# FPGA_POWER.net
KiCad netlist of a schematic drawn in Altium Designer
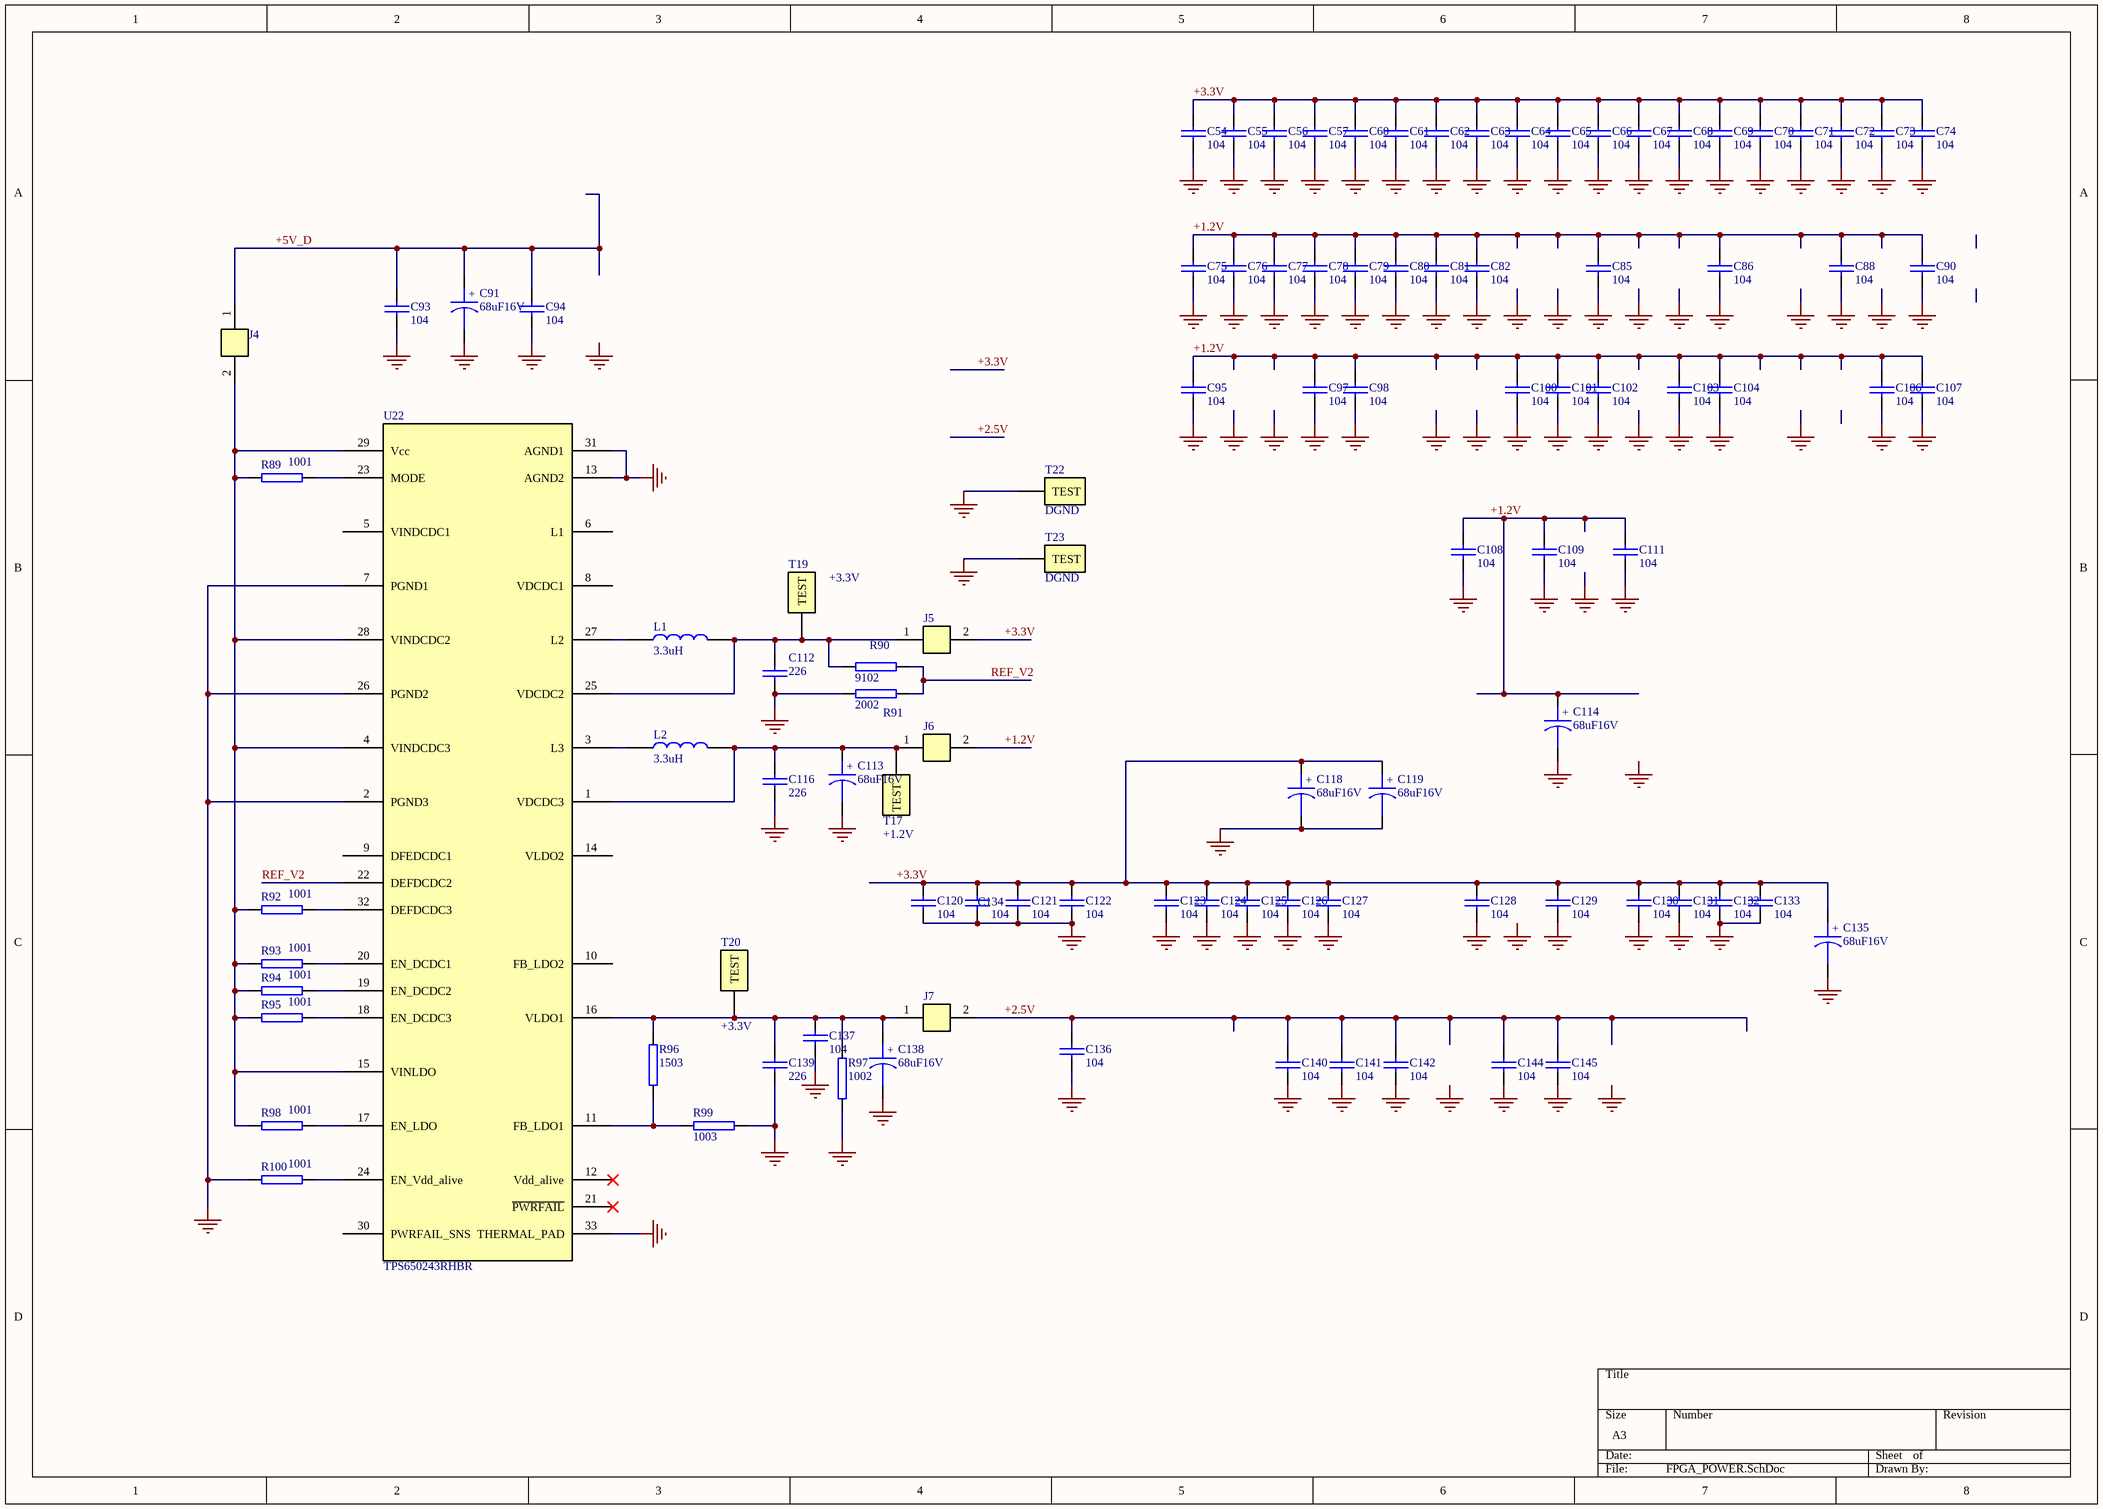
[diagram p0: FPGA_POWER.SchDoc]

(export (version "E")
  (design (tool "Eeschema 10.0.6"))
  (components
    (comp (ref "C54")
      (value "104")
      (footprint "0805C")
      (description "Capacitor")
      (libsource (lib "*") (part "CAP"))
    )
    (comp (ref "C55")
      (value "104")
      (footprint "0402C")
      (description "Capacitor")
      (libsource (lib "*") (part "CAP"))
    )
    (comp (ref "C56")
      (value "104")
      (footprint "0402C")
      (description "Capacitor")
      (libsource (lib "*") (part "CAP"))
    )
    (comp (ref "C57")
      (value "104")
      (footprint "0402C")
      (description "Capacitor")
      (libsource (lib "*") (part "CAP"))
    )
    (comp (ref "C60")
      (value "104")
      (footprint "0402C")
      (description "Capacitor")
      (libsource (lib "*") (part "CAP"))
    )
    (comp (ref "C61")
      (value "104")
      (footprint "0402C")
      (description "Capacitor")
      (libsource (lib "*") (part "CAP"))
    )
    (comp (ref "C62")
      (value "104")
      (footprint "0402C")
      (description "Capacitor")
      (libsource (lib "*") (part "CAP"))
    )
    (comp (ref "C63")
      (value "104")
      (footprint "0402C")
      (description "Capacitor")
      (libsource (lib "*") (part "CAP"))
    )
    (comp (ref "C64")
      (value "104")
      (footprint "0402C")
      (description "Capacitor")
      (libsource (lib "*") (part "CAP"))
    )
    (comp (ref "C65")
      (value "104")
      (footprint "0402C")
      (description "Capacitor")
      (libsource (lib "*") (part "CAP"))
    )
    (comp (ref "C66")
      (value "104")
      (footprint "0402C")
      (description "Capacitor")
      (libsource (lib "*") (part "CAP"))
    )
    (comp (ref "C67")
      (value "104")
      (footprint "0402C")
      (description "Capacitor")
      (libsource (lib "*") (part "CAP"))
    )
    (comp (ref "C68")
      (value "104")
      (footprint "0402C")
      (description "Capacitor")
      (libsource (lib "*") (part "CAP"))
    )
    (comp (ref "C69")
      (value "104")
      (footprint "0402C")
      (description "Capacitor")
      (libsource (lib "*") (part "CAP"))
    )
    (comp (ref "C70")
      (value "104")
      (footprint "0402C")
      (description "Capacitor")
      (libsource (lib "*") (part "CAP"))
    )
    (comp (ref "C71")
      (value "104")
      (footprint "0402C")
      (description "Capacitor")
      (libsource (lib "*") (part "CAP"))
    )
    (comp (ref "C72")
      (value "104")
      (footprint "0402C")
      (description "Capacitor")
      (libsource (lib "*") (part "CAP"))
    )
    (comp (ref "C73")
      (value "104")
      (footprint "0402C")
      (description "Capacitor")
      (libsource (lib "*") (part "CAP"))
    )
    (comp (ref "C74")
      (value "104")
      (footprint "0402C")
      (description "Capacitor")
      (libsource (lib "*") (part "CAP"))
    )
    (comp (ref "C75")
      (value "104")
      (footprint "0805C")
      (description "Capacitor")
      (libsource (lib "*") (part "CAP"))
    )
    (comp (ref "C76")
      (value "104")
      (footprint "0402C")
      (description "Capacitor")
      (libsource (lib "*") (part "CAP"))
    )
    (comp (ref "C77")
      (value "104")
      (footprint "0402C")
      (description "Capacitor")
      (libsource (lib "*") (part "CAP"))
    )
    (comp (ref "C78")
      (value "104")
      (footprint "0805C")
      (description "Capacitor")
      (libsource (lib "*") (part "CAP"))
    )
    (comp (ref "C79")
      (value "104")
      (footprint "0402C")
      (description "Capacitor")
      (libsource (lib "*") (part "CAP"))
    )
    (comp (ref "C80")
      (value "104")
      (footprint "0402C")
      (description "Capacitor")
      (libsource (lib "*") (part "CAP"))
    )
    (comp (ref "C81")
      (value "104")
      (footprint "0402C")
      (description "Capacitor")
      (libsource (lib "*") (part "CAP"))
    )
    (comp (ref "C82")
      (value "104")
      (footprint "0402C")
      (description "Capacitor")
      (libsource (lib "*") (part "CAP"))
    )
    (comp (ref "C85")
      (value "104")
      (footprint "0402C")
      (description "Capacitor")
      (libsource (lib "*") (part "CAP"))
    )
    (comp (ref "C86")
      (value "104")
      (footprint "0402C")
      (description "Capacitor")
      (libsource (lib "*") (part "CAP"))
    )
    (comp (ref "C88")
      (value "104")
      (footprint "0402C")
      (description "Capacitor")
      (libsource (lib "*") (part "CAP"))
    )
    (comp (ref "C90")
      (value "104")
      (footprint "0402C")
      (description "Capacitor")
      (libsource (lib "*") (part "CAP"))
    )
    (comp (ref "C91")
      (value "68uF16V")
      (footprint "6032")
      (description "Capacitor")
      (libsource (lib "*") (part "CAPACITOR POL"))
    )
    (comp (ref "C93")
      (value "104")
      (footprint "0805C")
      (description "Capacitor")
      (libsource (lib "*") (part "CAP"))
    )
    (comp (ref "C94")
      (value "104")
      (footprint "0805C")
      (description "Capacitor")
      (libsource (lib "*") (part "CAP"))
    )
    (comp (ref "C95")
      (value "104")
      (footprint "0402C")
      (description "Capacitor")
      (libsource (lib "*") (part "CAP"))
    )
    (comp (ref "C97")
      (value "104")
      (footprint "0402C")
      (description "Capacitor")
      (libsource (lib "*") (part "CAP"))
    )
    (comp (ref "C98")
      (value "104")
      (footprint "0402C")
      (description "Capacitor")
      (libsource (lib "*") (part "CAP"))
    )
    (comp (ref "C100")
      (value "104")
      (footprint "0402C")
      (description "Capacitor")
      (libsource (lib "*") (part "CAP"))
    )
    (comp (ref "C101")
      (value "104")
      (footprint "0402C")
      (description "Capacitor")
      (libsource (lib "*") (part "CAP"))
    )
    (comp (ref "C102")
      (value "104")
      (footprint "0402C")
      (description "Capacitor")
      (libsource (lib "*") (part "CAP"))
    )
    (comp (ref "C103")
      (value "104")
      (footprint "0402C")
      (description "Capacitor")
      (libsource (lib "*") (part "CAP"))
    )
    (comp (ref "C104")
      (value "104")
      (footprint "0402C")
      (description "Capacitor")
      (libsource (lib "*") (part "CAP"))
    )
    (comp (ref "C106")
      (value "104")
      (footprint "0402C")
      (description "Capacitor")
      (libsource (lib "*") (part "CAP"))
    )
    (comp (ref "C107")
      (value "104")
      (footprint "0402C")
      (description "Capacitor")
      (libsource (lib "*") (part "CAP"))
    )
    (comp (ref "C108")
      (value "104")
      (footprint "0402C")
      (description "Capacitor")
      (libsource (lib "*") (part "CAP"))
    )
    (comp (ref "C109")
      (value "104")
      (footprint "0402C")
      (description "Capacitor")
      (libsource (lib "*") (part "CAP"))
    )
    (comp (ref "C111")
      (value "104")
      (footprint "0402C")
      (description "Capacitor")
      (libsource (lib "*") (part "CAP"))
    )
    (comp (ref "C112")
      (value "226")
      (footprint "C226")
      (description "Capacitor")
      (libsource (lib "*") (part "CAP"))
    )
    (comp (ref "C113")
      (value "68uF16V")
      (footprint "6032")
      (description "Capacitor")
      (libsource (lib "*") (part "CAPACITOR POL"))
    )
    (comp (ref "C114")
      (value "68uF16V")
      (footprint "6032")
      (description "Capacitor")
      (libsource (lib "*") (part "CAPACITOR POL"))
    )
    (comp (ref "C116")
      (value "226")
      (footprint "C226")
      (description "Capacitor")
      (libsource (lib "*") (part "CAP"))
    )
    (comp (ref "C118")
      (value "68uF16V")
      (footprint "6032")
      (description "Capacitor")
      (libsource (lib "*") (part "CAPACITOR POL"))
    )
    (comp (ref "C119")
      (value "68uF16V")
      (footprint "6032")
      (description "Capacitor")
      (libsource (lib "*") (part "CAPACITOR POL"))
    )
    (comp (ref "C120")
      (value "104")
      (footprint "0402C")
      (description "Capacitor")
      (libsource (lib "*") (part "CAP"))
    )
    (comp (ref "C121")
      (value "104")
      (footprint "0402C")
      (description "Capacitor")
      (libsource (lib "*") (part "CAP"))
    )
    (comp (ref "C122")
      (value "104")
      (footprint "0805C")
      (description "Capacitor")
      (libsource (lib "*") (part "CAP"))
    )
    (comp (ref "C123")
      (value "104")
      (footprint "0805C")
      (description "Capacitor")
      (libsource (lib "*") (part "CAP"))
    )
    (comp (ref "C124")
      (value "104")
      (footprint "0805C")
      (description "Capacitor")
      (libsource (lib "*") (part "CAP"))
    )
    (comp (ref "C125")
      (value "104")
      (footprint "0805C")
      (description "Capacitor")
      (libsource (lib "*") (part "CAP"))
    )
    (comp (ref "C126")
      (value "104")
      (footprint "0805C")
      (description "Capacitor")
      (libsource (lib "*") (part "CAP"))
    )
    (comp (ref "C127")
      (value "104")
      (footprint "0402C")
      (description "Capacitor")
      (libsource (lib "*") (part "CAP"))
    )
    (comp (ref "C128")
      (value "104")
      (footprint "0805C")
      (description "Capacitor")
      (libsource (lib "*") (part "CAP"))
    )
    (comp (ref "C129")
      (value "104")
      (footprint "0402C")
      (description "Capacitor")
      (libsource (lib "*") (part "CAP"))
    )
    (comp (ref "C130")
      (value "104")
      (footprint "0402C")
      (description "Capacitor")
      (libsource (lib "*") (part "CAP"))
    )
    (comp (ref "C131")
      (value "104")
      (footprint "0402C")
      (description "Capacitor")
      (libsource (lib "*") (part "CAP"))
    )
    (comp (ref "C132")
      (value "104")
      (footprint "0402C")
      (description "Capacitor")
      (libsource (lib "*") (part "CAP"))
    )
    (comp (ref "C133")
      (value "104")
      (footprint "0402C")
      (description "Capacitor")
      (libsource (lib "*") (part "CAP"))
    )
    (comp (ref "C134")
      (value "104")
      (footprint "0402C")
      (description "Capacitor")
      (libsource (lib "*") (part "CAP"))
    )
    (comp (ref "C135")
      (value "68uF16V")
      (footprint "6032")
      (description "Capacitor")
      (libsource (lib "*") (part "CAPACITOR POL"))
    )
    (comp (ref "C136")
      (value "104")
      (footprint "0805C")
      (description "Capacitor")
      (libsource (lib "*") (part "CAP"))
    )
    (comp (ref "C137")
      (value "104")
      (footprint "0805C")
      (description "Capacitor")
      (libsource (lib "*") (part "CAP"))
    )
    (comp (ref "C138")
      (value "68uF16V")
      (footprint "6032")
      (description "Capacitor")
      (libsource (lib "*") (part "CAPACITOR POL"))
    )
    (comp (ref "C139")
      (value "226")
      (footprint "C226")
      (description "Capacitor")
      (libsource (lib "*") (part "CAP"))
    )
    (comp (ref "C140")
      (value "104")
      (footprint "0402C")
      (description "Capacitor")
      (libsource (lib "*") (part "CAP"))
    )
    (comp (ref "C141")
      (value "104")
      (footprint "0402C")
      (description "Capacitor")
      (libsource (lib "*") (part "CAP"))
    )
    (comp (ref "C142")
      (value "104")
      (footprint "0402C")
      (description "Capacitor")
      (libsource (lib "*") (part "CAP"))
    )
    (comp (ref "C144")
      (value "104")
      (footprint "0805C")
      (description "Capacitor")
      (libsource (lib "*") (part "CAP"))
    )
    (comp (ref "C145")
      (value "104")
      (footprint "0402C")
      (description "Capacitor")
      (libsource (lib "*") (part "CAP"))
    )
    (comp (ref "J4") (value "~") (footprint "I_ON1") (libsource (lib "") (part "I_ON_1")))
    (comp (ref "J5") (value "~") (footprint "I_ON1") (libsource (lib "*") (part "I_ON")))
    (comp (ref "J6") (value "~") (footprint "I_ON1") (libsource (lib "*") (part "I_ON")))
    (comp (ref "J7") (value "~") (footprint "I_ON1") (libsource (lib "*") (part "I_ON")))
    (comp (ref "L1") (value "3.3uH") (footprint "L3R3") (libsource (lib "*") (part "L")))
    (comp (ref "L2") (value "3.3uH") (footprint "L3R3") (libsource (lib "*") (part "L")))
    (comp (ref "R89") (value "1001") (footprint "0603") (libsource (lib "*") (part "RES2")))
    (comp (ref "R90") (value "9102") (footprint "0603") (libsource (lib "*") (part "RES2")))
    (comp (ref "R91") (value "2002") (footprint "0603") (libsource (lib "*") (part "RES2")))
    (comp (ref "R92") (value "1001") (footprint "0603") (libsource (lib "*") (part "RES2")))
    (comp (ref "R93") (value "1001") (footprint "0603") (libsource (lib "*") (part "RES2")))
    (comp (ref "R94") (value "1001") (footprint "0603") (libsource (lib "*") (part "RES2")))
    (comp (ref "R95") (value "1001") (footprint "0603") (libsource (lib "*") (part "RES2")))
    (comp (ref "R96") (value "1503") (footprint "0603") (libsource (lib "*") (part "RES2")))
    (comp (ref "R97") (value "1002") (footprint "0603") (libsource (lib "") (part "RES2_1")))
    (comp (ref "R98") (value "1001") (footprint "0603") (libsource (lib "*") (part "RES2")))
    (comp (ref "R99") (value "1003") (footprint "0603") (libsource (lib "*") (part "RES2")))
    (comp (ref "R100") (value "1001") (footprint "0603") (libsource (lib "*") (part "RES2")))
    (comp (ref "T17") (value "+1.2V") (footprint "TEST") (libsource (lib "USB30_Project") (part "TEST")))
    (comp (ref "T19") (value "+3.3V") (footprint "TEST") (libsource (lib "") (part "TEST_1")))
    (comp (ref "T20") (value "+3.3V") (footprint "TEST") (libsource (lib "") (part "TEST_1")))
    (comp (ref "T22") (value "DGND") (footprint "TEST") (libsource (lib "") (part "TEST_2")))
    (comp (ref "T23") (value "DGND") (footprint "TEST") (libsource (lib "") (part "TEST_2")))
    (comp (ref "U22") (value "TPS650243RHBR") (footprint "VQFN32") (libsource (lib "*") (part "TPS650243")))
  )
  (nets
    (net (code "1") (name "/+1.2V") (class "Default")
      (node (ref "C100") (pin "2") (pinfunction "2_2") (pintype "passive"))
      (node (ref "C101") (pin "2") (pinfunction "2_2") (pintype "passive"))
      (node (ref "C102") (pin "2") (pinfunction "2_2") (pintype "passive"))
      (node (ref "C103") (pin "2") (pinfunction "2_2") (pintype "passive"))
      (node (ref "C104") (pin "2") (pinfunction "2_2") (pintype "passive"))
      (node (ref "C106") (pin "2") (pinfunction "2_2") (pintype "passive"))
      (node (ref "C107") (pin "2") (pinfunction "2_2") (pintype "passive"))
      (node (ref "C108") (pin "2") (pinfunction "2_2") (pintype "passive"))
      (node (ref "C109") (pin "2") (pinfunction "2_2") (pintype "passive"))
      (node (ref "C111") (pin "2") (pinfunction "2_2") (pintype "passive"))
      (node (ref "C114") (pin "1") (pinfunction "1_1") (pintype "passive"))
      (node (ref "C75") (pin "2") (pinfunction "2_2") (pintype "passive"))
      (node (ref "C76") (pin "2") (pinfunction "2_2") (pintype "passive"))
      (node (ref "C77") (pin "2") (pinfunction "2_2") (pintype "passive"))
      (node (ref "C78") (pin "2") (pinfunction "2_2") (pintype "passive"))
      (node (ref "C79") (pin "2") (pinfunction "2_2") (pintype "passive"))
      (node (ref "C80") (pin "2") (pinfunction "2_2") (pintype "passive"))
      (node (ref "C81") (pin "2") (pinfunction "2_2") (pintype "passive"))
      (node (ref "C82") (pin "2") (pinfunction "2_2") (pintype "passive"))
      (node (ref "C85") (pin "2") (pinfunction "2_2") (pintype "passive"))
      (node (ref "C86") (pin "2") (pinfunction "2_2") (pintype "passive"))
      (node (ref "C88") (pin "2") (pinfunction "2_2") (pintype "passive"))
      (node (ref "C90") (pin "2") (pinfunction "2_2") (pintype "passive"))
      (node (ref "C95") (pin "2") (pinfunction "2_2") (pintype "passive"))
      (node (ref "C97") (pin "2") (pinfunction "2_2") (pintype "passive"))
      (node (ref "C98") (pin "2") (pinfunction "2_2") (pintype "passive"))
      (node (ref "J6") (pin "2") (pintype "passive"))
    )
    (net (code "2") (name "/+2.5V") (class "Default")
      (node (ref "C136") (pin "2") (pinfunction "2_2") (pintype "passive"))
      (node (ref "C140") (pin "2") (pinfunction "2_2") (pintype "passive"))
      (node (ref "C141") (pin "2") (pinfunction "2_2") (pintype "passive"))
      (node (ref "C142") (pin "2") (pinfunction "2_2") (pintype "passive"))
      (node (ref "C144") (pin "2") (pinfunction "2_2") (pintype "passive"))
      (node (ref "C145") (pin "2") (pinfunction "2_2") (pintype "passive"))
      (node (ref "J7") (pin "2") (pintype "passive"))
    )
    (net (code "3") (name "/+3.3V") (class "Default")
      (node (ref "C118") (pin "1") (pinfunction "1_1") (pintype "passive"))
      (node (ref "C119") (pin "1") (pinfunction "1_1") (pintype "passive"))
      (node (ref "C120") (pin "2") (pinfunction "2_2") (pintype "passive"))
      (node (ref "C121") (pin "2") (pinfunction "2_2") (pintype "passive"))
      (node (ref "C122") (pin "2") (pinfunction "2_2") (pintype "passive"))
      (node (ref "C123") (pin "2") (pinfunction "2_2") (pintype "passive"))
      (node (ref "C124") (pin "2") (pinfunction "2_2") (pintype "passive"))
      (node (ref "C125") (pin "2") (pinfunction "2_2") (pintype "passive"))
      (node (ref "C126") (pin "2") (pinfunction "2_2") (pintype "passive"))
      (node (ref "C127") (pin "2") (pinfunction "2_2") (pintype "passive"))
      (node (ref "C128") (pin "2") (pinfunction "2_2") (pintype "passive"))
      (node (ref "C129") (pin "2") (pinfunction "2_2") (pintype "passive"))
      (node (ref "C130") (pin "2") (pinfunction "2_2") (pintype "passive"))
      (node (ref "C131") (pin "2") (pinfunction "2_2") (pintype "passive"))
      (node (ref "C132") (pin "2") (pinfunction "2_2") (pintype "passive"))
      (node (ref "C133") (pin "2") (pinfunction "2_2") (pintype "passive"))
      (node (ref "C134") (pin "2") (pinfunction "2_2") (pintype "passive"))
      (node (ref "C135") (pin "1") (pinfunction "1_1") (pintype "passive"))
      (node (ref "C54") (pin "2") (pinfunction "2_2") (pintype "passive"))
      (node (ref "C55") (pin "2") (pinfunction "2_2") (pintype "passive"))
      (node (ref "C56") (pin "2") (pinfunction "2_2") (pintype "passive"))
      (node (ref "C57") (pin "2") (pinfunction "2_2") (pintype "passive"))
      (node (ref "C60") (pin "2") (pinfunction "2_2") (pintype "passive"))
      (node (ref "C61") (pin "2") (pinfunction "2_2") (pintype "passive"))
      (node (ref "C62") (pin "2") (pinfunction "2_2") (pintype "passive"))
      (node (ref "C63") (pin "2") (pinfunction "2_2") (pintype "passive"))
      (node (ref "C64") (pin "2") (pinfunction "2_2") (pintype "passive"))
      (node (ref "C65") (pin "2") (pinfunction "2_2") (pintype "passive"))
      (node (ref "C66") (pin "2") (pinfunction "2_2") (pintype "passive"))
      (node (ref "C67") (pin "2") (pinfunction "2_2") (pintype "passive"))
      (node (ref "C68") (pin "2") (pinfunction "2_2") (pintype "passive"))
      (node (ref "C69") (pin "2") (pinfunction "2_2") (pintype "passive"))
      (node (ref "C70") (pin "2") (pinfunction "2_2") (pintype "passive"))
      (node (ref "C71") (pin "2") (pinfunction "2_2") (pintype "passive"))
      (node (ref "C72") (pin "2") (pinfunction "2_2") (pintype "passive"))
      (node (ref "C73") (pin "2") (pinfunction "2_2") (pintype "passive"))
      (node (ref "C74") (pin "2") (pinfunction "2_2") (pintype "passive"))
      (node (ref "J5") (pin "2") (pintype "passive"))
    )
    (net (code "4") (name "/+5V_D") (class "Default")
      (node (ref "C91") (pin "1") (pinfunction "1_1") (pintype "passive"))
      (node (ref "C93") (pin "2") (pinfunction "2_2") (pintype "passive"))
      (node (ref "C94") (pin "2") (pinfunction "2_2") (pintype "passive"))
      (node (ref "J4") (pin "1") (pintype "passive"))
    )
    (net (code "5") (name "/REF_V2") (class "Default")
      (node (ref "R90") (pin "2") (pinfunction "2_2") (pintype "passive"))
      (node (ref "R91") (pin "1") (pinfunction "1_1") (pintype "passive"))
      (node (ref "U22") (pin "22") (pinfunction "DEFDCDC2_22") (pintype "passive"))
    )
    (net (code "6") (name "DGND") (class "Default")
      (node (ref "C100") (pin "1") (pinfunction "1_1") (pintype "passive"))
      (node (ref "C101") (pin "1") (pinfunction "1_1") (pintype "passive"))
      (node (ref "C102") (pin "1") (pinfunction "1_1") (pintype "passive"))
      (node (ref "C103") (pin "1") (pinfunction "1_1") (pintype "passive"))
      (node (ref "C104") (pin "1") (pinfunction "1_1") (pintype "passive"))
      (node (ref "C106") (pin "1") (pinfunction "1_1") (pintype "passive"))
      (node (ref "C107") (pin "1") (pinfunction "1_1") (pintype "passive"))
      (node (ref "C108") (pin "1") (pinfunction "1_1") (pintype "passive"))
      (node (ref "C109") (pin "1") (pinfunction "1_1") (pintype "passive"))
      (node (ref "C111") (pin "1") (pinfunction "1_1") (pintype "passive"))
      (node (ref "C112") (pin "2") (pinfunction "2_2") (pintype "passive"))
      (node (ref "C113") (pin "2") (pinfunction "2_2") (pintype "passive"))
      (node (ref "C114") (pin "2") (pinfunction "2_2") (pintype "passive"))
      (node (ref "C116") (pin "2") (pinfunction "2_2") (pintype "passive"))
      (node (ref "C118") (pin "2") (pinfunction "2_2") (pintype "passive"))
      (node (ref "C119") (pin "2") (pinfunction "2_2") (pintype "passive"))
      (node (ref "C120") (pin "1") (pinfunction "1_1") (pintype "passive"))
      (node (ref "C121") (pin "1") (pinfunction "1_1") (pintype "passive"))
      (node (ref "C122") (pin "1") (pinfunction "1_1") (pintype "passive"))
      (node (ref "C123") (pin "1") (pinfunction "1_1") (pintype "passive"))
      (node (ref "C124") (pin "1") (pinfunction "1_1") (pintype "passive"))
      (node (ref "C125") (pin "1") (pinfunction "1_1") (pintype "passive"))
      (node (ref "C126") (pin "1") (pinfunction "1_1") (pintype "passive"))
      (node (ref "C127") (pin "1") (pinfunction "1_1") (pintype "passive"))
      (node (ref "C128") (pin "1") (pinfunction "1_1") (pintype "passive"))
      (node (ref "C129") (pin "1") (pinfunction "1_1") (pintype "passive"))
      (node (ref "C130") (pin "1") (pinfunction "1_1") (pintype "passive"))
      (node (ref "C131") (pin "1") (pinfunction "1_1") (pintype "passive"))
      (node (ref "C132") (pin "1") (pinfunction "1_1") (pintype "passive"))
      (node (ref "C133") (pin "1") (pinfunction "1_1") (pintype "passive"))
      (node (ref "C134") (pin "1") (pinfunction "1_1") (pintype "passive"))
      (node (ref "C135") (pin "2") (pinfunction "2_2") (pintype "passive"))
      (node (ref "C136") (pin "1") (pinfunction "1_1") (pintype "passive"))
      (node (ref "C137") (pin "1") (pinfunction "1_1") (pintype "passive"))
      (node (ref "C138") (pin "2") (pinfunction "2_2") (pintype "passive"))
      (node (ref "C139") (pin "2") (pinfunction "2_2") (pintype "passive"))
      (node (ref "C140") (pin "1") (pinfunction "1_1") (pintype "passive"))
      (node (ref "C141") (pin "1") (pinfunction "1_1") (pintype "passive"))
      (node (ref "C142") (pin "1") (pinfunction "1_1") (pintype "passive"))
      (node (ref "C144") (pin "1") (pinfunction "1_1") (pintype "passive"))
      (node (ref "C145") (pin "1") (pinfunction "1_1") (pintype "passive"))
      (node (ref "C54") (pin "1") (pinfunction "1_1") (pintype "passive"))
      (node (ref "C55") (pin "1") (pinfunction "1_1") (pintype "passive"))
      (node (ref "C56") (pin "1") (pinfunction "1_1") (pintype "passive"))
      (node (ref "C57") (pin "1") (pinfunction "1_1") (pintype "passive"))
      (node (ref "C60") (pin "1") (pinfunction "1_1") (pintype "passive"))
      (node (ref "C61") (pin "1") (pinfunction "1_1") (pintype "passive"))
      (node (ref "C62") (pin "1") (pinfunction "1_1") (pintype "passive"))
      (node (ref "C63") (pin "1") (pinfunction "1_1") (pintype "passive"))
      (node (ref "C64") (pin "1") (pinfunction "1_1") (pintype "passive"))
      (node (ref "C65") (pin "1") (pinfunction "1_1") (pintype "passive"))
      (node (ref "C66") (pin "1") (pinfunction "1_1") (pintype "passive"))
      (node (ref "C67") (pin "1") (pinfunction "1_1") (pintype "passive"))
      (node (ref "C68") (pin "1") (pinfunction "1_1") (pintype "passive"))
      (node (ref "C69") (pin "1") (pinfunction "1_1") (pintype "passive"))
      (node (ref "C70") (pin "1") (pinfunction "1_1") (pintype "passive"))
      (node (ref "C71") (pin "1") (pinfunction "1_1") (pintype "passive"))
      (node (ref "C72") (pin "1") (pinfunction "1_1") (pintype "passive"))
      (node (ref "C73") (pin "1") (pinfunction "1_1") (pintype "passive"))
      (node (ref "C74") (pin "1") (pinfunction "1_1") (pintype "passive"))
      (node (ref "C75") (pin "1") (pinfunction "1_1") (pintype "passive"))
      (node (ref "C76") (pin "1") (pinfunction "1_1") (pintype "passive"))
      (node (ref "C77") (pin "1") (pinfunction "1_1") (pintype "passive"))
      (node (ref "C78") (pin "1") (pinfunction "1_1") (pintype "passive"))
      (node (ref "C79") (pin "1") (pinfunction "1_1") (pintype "passive"))
      (node (ref "C80") (pin "1") (pinfunction "1_1") (pintype "passive"))
      (node (ref "C81") (pin "1") (pinfunction "1_1") (pintype "passive"))
      (node (ref "C82") (pin "1") (pinfunction "1_1") (pintype "passive"))
      (node (ref "C85") (pin "1") (pinfunction "1_1") (pintype "passive"))
      (node (ref "C86") (pin "1") (pinfunction "1_1") (pintype "passive"))
      (node (ref "C88") (pin "1") (pinfunction "1_1") (pintype "passive"))
      (node (ref "C90") (pin "1") (pinfunction "1_1") (pintype "passive"))
      (node (ref "C91") (pin "2") (pinfunction "2_2") (pintype "passive"))
      (node (ref "C93") (pin "1") (pinfunction "1_1") (pintype "passive"))
      (node (ref "C94") (pin "1") (pinfunction "1_1") (pintype "passive"))
      (node (ref "C95") (pin "1") (pinfunction "1_1") (pintype "passive"))
      (node (ref "C97") (pin "1") (pinfunction "1_1") (pintype "passive"))
      (node (ref "C98") (pin "1") (pinfunction "1_1") (pintype "passive"))
      (node (ref "R100") (pin "1") (pinfunction "1_1") (pintype "passive"))
      (node (ref "R91") (pin "2") (pinfunction "2_2") (pintype "passive"))
      (node (ref "R97") (pin "2") (pinfunction "2_2") (pintype "passive"))
      (node (ref "R99") (pin "2") (pinfunction "2_2") (pintype "passive"))
      (node (ref "T22") (pin "1") (pinfunction "TEST_1") (pintype "passive"))
      (node (ref "T23") (pin "1") (pinfunction "TEST_1") (pintype "passive"))
      (node (ref "U22") (pin "13") (pinfunction "AGND2_13") (pintype "passive"))
      (node (ref "U22") (pin "2") (pinfunction "PGND3_2") (pintype "passive"))
      (node (ref "U22") (pin "26") (pinfunction "PGND2_26") (pintype "passive"))
      (node (ref "U22") (pin "31") (pinfunction "AGND1_31") (pintype "passive"))
      (node (ref "U22") (pin "33") (pinfunction "THERMAL_PAD_33") (pintype "passive"))
      (node (ref "U22") (pin "7") (pinfunction "PGND1_7") (pintype "passive"))
    )
    (net (code "7") (name "Net-(T17-TEST)") (class "Default")
      (node (ref "C113") (pin "1") (pinfunction "1_1") (pintype "passive"))
      (node (ref "C116") (pin "1") (pinfunction "1_1") (pintype "passive"))
      (node (ref "J6") (pin "1") (pintype "passive"))
      (node (ref "L2") (pin "2") (pinfunction "2_2") (pintype "passive"))
      (node (ref "T17") (pin "1") (pinfunction "TEST_1") (pintype "passive"))
      (node (ref "U22") (pin "1") (pinfunction "VDCDC3_1") (pintype "passive"))
    )
    (net (code "8") (name "Net-(T19-TEST)") (class "Default")
      (node (ref "C112") (pin "1") (pinfunction "1_1") (pintype "passive"))
      (node (ref "J5") (pin "1") (pintype "passive"))
      (node (ref "L1") (pin "2") (pinfunction "2_2") (pintype "passive"))
      (node (ref "R90") (pin "1") (pinfunction "1_1") (pintype "passive"))
      (node (ref "T19") (pin "1") (pinfunction "TEST_1") (pintype "passive"))
      (node (ref "U22") (pin "25") (pinfunction "VDCDC2_25") (pintype "passive"))
    )
    (net (code "9") (name "Net-(T20-TEST)") (class "Default")
      (node (ref "C137") (pin "2") (pinfunction "2_2") (pintype "passive"))
      (node (ref "C138") (pin "1") (pinfunction "1_1") (pintype "passive"))
      (node (ref "C139") (pin "1") (pinfunction "1_1") (pintype "passive"))
      (node (ref "J7") (pin "1") (pintype "passive"))
      (node (ref "R96") (pin "2") (pinfunction "2_2") (pintype "passive"))
      (node (ref "R97") (pin "1") (pinfunction "1_1") (pintype "passive"))
      (node (ref "T20") (pin "1") (pinfunction "TEST_1") (pintype "passive"))
      (node (ref "U22") (pin "16") (pinfunction "VLDO1_16") (pintype "passive"))
    )
    (net (code "10") (name "Net-(U22-DEFDCDC3)") (class "Default")
      (node (ref "R92") (pin "2") (pinfunction "2_2") (pintype "passive"))
      (node (ref "U22") (pin "32") (pinfunction "DEFDCDC3_32") (pintype "passive"))
    )
    (net (code "11") (name "Net-(U22-EN_DCDC1)") (class "Default")
      (node (ref "R93") (pin "2") (pinfunction "2_2") (pintype "passive"))
      (node (ref "U22") (pin "20") (pinfunction "EN_DCDC1_20") (pintype "passive"))
    )
    (net (code "12") (name "Net-(U22-EN_DCDC2)") (class "Default")
      (node (ref "R94") (pin "2") (pinfunction "2_2") (pintype "passive"))
      (node (ref "U22") (pin "19") (pinfunction "EN_DCDC2_19") (pintype "passive"))
    )
    (net (code "13") (name "Net-(U22-EN_DCDC3)") (class "Default")
      (node (ref "R95") (pin "2") (pinfunction "2_2") (pintype "passive"))
      (node (ref "U22") (pin "18") (pinfunction "EN_DCDC3_18") (pintype "passive"))
    )
    (net (code "14") (name "Net-(U22-EN_LDO)") (class "Default")
      (node (ref "R98") (pin "2") (pinfunction "2_2") (pintype "passive"))
      (node (ref "U22") (pin "17") (pinfunction "EN_LDO_17") (pintype "passive"))
    )
    (net (code "15") (name "Net-(U22-EN_Vdd_alive)") (class "Default")
      (node (ref "R100") (pin "2") (pinfunction "2_2") (pintype "passive"))
      (node (ref "U22") (pin "24") (pinfunction "EN_Vdd_alive_24") (pintype "passive"))
    )
    (net (code "16") (name "Net-(U22-FB_LDO1)") (class "Default")
      (node (ref "R96") (pin "1") (pinfunction "1_1") (pintype "passive"))
      (node (ref "R99") (pin "1") (pinfunction "1_1") (pintype "passive"))
      (node (ref "U22") (pin "11") (pinfunction "FB_LDO1_11") (pintype "passive"))
    )
    (net (code "17") (name "Net-(U22-L2)") (class "Default")
      (node (ref "L1") (pin "1") (pinfunction "1_1") (pintype "passive"))
      (node (ref "U22") (pin "27") (pinfunction "L2_27") (pintype "passive"))
    )
    (net (code "18") (name "Net-(U22-L3)") (class "Default")
      (node (ref "L2") (pin "1") (pinfunction "1_1") (pintype "passive"))
      (node (ref "U22") (pin "3") (pinfunction "L3_3") (pintype "passive"))
    )
    (net (code "19") (name "Net-(U22-MODE)") (class "Default")
      (node (ref "R89") (pin "2") (pinfunction "2_2") (pintype "passive"))
      (node (ref "U22") (pin "23") (pinfunction "MODE_23") (pintype "passive"))
    )
    (net (code "20") (name "Net-(U22-VINDCDC2)") (class "Default")
      (node (ref "J4") (pin "2") (pintype "passive"))
      (node (ref "R89") (pin "1") (pinfunction "1_1") (pintype "passive"))
      (node (ref "R92") (pin "1") (pinfunction "1_1") (pintype "passive"))
      (node (ref "R93") (pin "1") (pinfunction "1_1") (pintype "passive"))
      (node (ref "R94") (pin "1") (pinfunction "1_1") (pintype "passive"))
      (node (ref "R95") (pin "1") (pinfunction "1_1") (pintype "passive"))
      (node (ref "R98") (pin "1") (pinfunction "1_1") (pintype "passive"))
      (node (ref "U22") (pin "15") (pinfunction "VINLDO_15") (pintype "passive"))
      (node (ref "U22") (pin "28") (pinfunction "VINDCDC2_28") (pintype "passive"))
      (node (ref "U22") (pin "29") (pinfunction "Vcc_29") (pintype "passive"))
      (node (ref "U22") (pin "4") (pinfunction "VINDCDC3_4") (pintype "passive"))
    )
    (net (code "21") (name "unconnected-(U22-DFEDCDC1-Pad9)") (class "Default")
      (node (ref "U22") (pin "9") (pinfunction "DFEDCDC1_9") (pintype "passive"))
    )
    (net (code "22") (name "unconnected-(U22-FB_LDO2-Pad10)") (class "Default")
      (node (ref "U22") (pin "10") (pinfunction "FB_LDO2_10") (pintype "passive"))
    )
    (net (code "23") (name "unconnected-(U22-L1-Pad6)") (class "Default")
      (node (ref "U22") (pin "6") (pinfunction "L1_6") (pintype "passive"))
    )
    (net (code "24") (name "unconnected-(U22-PWRFAIL_SNS-Pad30)") (class "Default")
      (node (ref "U22") (pin "30") (pinfunction "PWRFAIL_SNS_30") (pintype "passive"))
    )
    (net (code "25") (name "unconnected-(U22-VDCDC1-Pad8)") (class "Default")
      (node (ref "U22") (pin "8") (pinfunction "VDCDC1_8") (pintype "passive"))
    )
    (net (code "26") (name "unconnected-(U22-VINDCDC1-Pad5)") (class "Default")
      (node (ref "U22") (pin "5") (pinfunction "VINDCDC1_5") (pintype "passive"))
    )
    (net (code "27") (name "unconnected-(U22-VLDO2-Pad14)") (class "Default")
      (node (ref "U22") (pin "14") (pinfunction "VLDO2_14") (pintype "passive"))
    )
    (net (code "28") (name "unconnected-(U22-Vdd_alive-Pad12)") (class "Default")
      (node (ref "U22") (pin "12") (pinfunction "Vdd_alive_12") (pintype "passive+no_connect"))
    )
    (net (code "29") (name "unconnected-(U22-~{PWRFAIL}-Pad21)") (class "Default")
      (node (ref "U22") (pin "21") (pinfunction "~{PWRFAIL}_21") (pintype "passive+no_connect"))
    )
  )
)
